# Battery3.net
KiCad netlist of a schematic drawn in Altium Designer
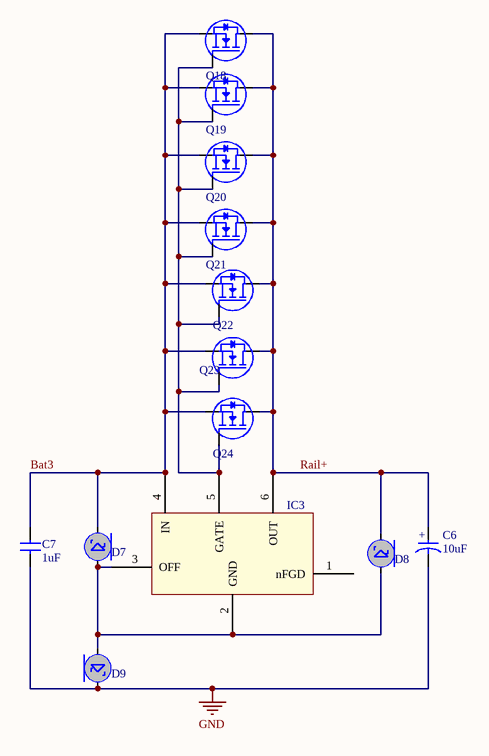
[diagram p0: Battery3.SchDoc]

(export (version "E")
  (design (tool "Eeschema 10.0.6"))
  (components
    (comp (ref "C6")
      (value "10uF")
      (footprint "CAP22uF100V")
      (fields (field (name "Comment") "CapPol"))
      (libsource (lib "SubjuGator8") (part "CapPol"))
    )
    (comp (ref "C7")
      (value "1uF")
      (footprint "CAPC1206")
      (fields (field (name "Comment") "Cap"))
      (libsource (lib "SubjuGator8") (part "Cap"))
    )
    (comp (ref "D7")
      (value "Schottky")
      (footprint "SS110-TP")
      (description "Schottky Diode Template")
      (libsource (lib "SubjuGator8") (part "Schottky"))
    )
    (comp (ref "D8")
      (value "SMBJ100A-13-F")
      (footprint "SMBJ100A-13-F")
      (description "TVS DIODE 100VWM 162VC SMB")
      (libsource (lib "SubjuGator8") (part "SMBJ100A-13-F"))
    )
    (comp (ref "D9")
      (value "Schottky")
      (footprint "SS110-TP")
      (description "Schottky Diode Template")
      (libsource (lib "") (part "Schottky_1"))
    )
    (comp (ref "IC3")
      (value "LM5050MK-2/NOPB")
      (footprint "LM5050MK-2/NOPB")
      (description "IC OR CTRLR N+1 6SOT")
      (libsource (lib "SubjuGator8") (part "LM5050MK-2/NOPB"))
    )
    (comp (ref "Q18")
      (value "CSD19502Q5B")
      (footprint "CSD19502Q5B")
      (description "NEXFET Power MOSFET")
      (libsource (lib "SubjuGator8") (part "CSD19502Q5B"))
    )
    (comp (ref "Q19")
      (value "CSD19502Q5B")
      (footprint "CSD19502Q5B")
      (description "NEXFET Power MOSFET")
      (libsource (lib "SubjuGator8") (part "CSD19502Q5B"))
    )
    (comp (ref "Q20")
      (value "CSD19502Q5B")
      (footprint "CSD19502Q5B")
      (description "NEXFET Power MOSFET")
      (libsource (lib "SubjuGator8") (part "CSD19502Q5B"))
    )
    (comp (ref "Q21")
      (value "CSD19502Q5B")
      (footprint "CSD19502Q5B")
      (description "NEXFET Power MOSFET")
      (libsource (lib "SubjuGator8") (part "CSD19502Q5B"))
    )
    (comp (ref "Q22")
      (value "CSD19502Q5B")
      (footprint "CSD19502Q5B")
      (description "NEXFET Power MOSFET")
      (libsource (lib "SubjuGator8") (part "CSD19502Q5B"))
    )
    (comp (ref "Q23")
      (value "CSD19502Q5B")
      (footprint "CSD19502Q5B")
      (description "NEXFET Power MOSFET")
      (libsource (lib "SubjuGator8") (part "CSD19502Q5B"))
    )
    (comp (ref "Q24")
      (value "CSD19502Q5B")
      (footprint "CSD19502Q5B")
      (description "NEXFET Power MOSFET")
      (libsource (lib "SubjuGator8") (part "CSD19502Q5B"))
    )
  )
  (nets
    (net (code "1") (name "/Bat3") (class "Default")
      (node (ref "C7") (pin "1") (pinfunction "A_1") (pintype "passive"))
      (node (ref "D7") (pin "C") (pinfunction "C_C") (pintype "passive"))
      (node (ref "IC3") (pin "4") (pinfunction "IN_4") (pintype "passive"))
      (node (ref "Q18") (pin "S") (pinfunction "S_S") (pintype "passive"))
      (node (ref "Q19") (pin "S") (pinfunction "S_S") (pintype "passive"))
      (node (ref "Q20") (pin "S") (pinfunction "S_S") (pintype "passive"))
      (node (ref "Q21") (pin "S") (pinfunction "S_S") (pintype "passive"))
      (node (ref "Q22") (pin "S") (pinfunction "S_S") (pintype "passive"))
      (node (ref "Q23") (pin "S") (pinfunction "S_S") (pintype "passive"))
      (node (ref "Q24") (pin "S") (pinfunction "S_S") (pintype "passive"))
    )
    (net (code "2") (name "/Rail+") (class "Default")
      (node (ref "C6") (pin "1") (pinfunction "A_1") (pintype "passive"))
      (node (ref "D8") (pin "C") (pinfunction "C_C") (pintype "passive"))
      (node (ref "IC3") (pin "6") (pinfunction "OUT_6") (pintype "passive"))
      (node (ref "Q18") (pin "D") (pinfunction "D_D") (pintype "passive"))
      (node (ref "Q19") (pin "D") (pinfunction "D_D") (pintype "passive"))
      (node (ref "Q20") (pin "D") (pinfunction "D_D") (pintype "passive"))
      (node (ref "Q21") (pin "D") (pinfunction "D_D") (pintype "passive"))
      (node (ref "Q22") (pin "D") (pinfunction "D_D") (pintype "passive"))
      (node (ref "Q23") (pin "D") (pinfunction "D_D") (pintype "passive"))
      (node (ref "Q24") (pin "D") (pinfunction "D_D") (pintype "passive"))
    )
    (net (code "3") (name "GND") (class "Default")
      (node (ref "C6") (pin "2") (pinfunction "B_2") (pintype "passive"))
      (node (ref "C7") (pin "2") (pinfunction "B_2") (pintype "passive"))
      (node (ref "D9") (pin "C") (pinfunction "C_C") (pintype "passive"))
    )
    (net (code "4") (name "Net-(IC3-GATE)") (class "Default")
      (node (ref "IC3") (pin "5") (pinfunction "GATE_5") (pintype "passive"))
      (node (ref "Q18") (pin "G") (pinfunction "G_G") (pintype "passive"))
      (node (ref "Q19") (pin "G") (pinfunction "G_G") (pintype "passive"))
      (node (ref "Q20") (pin "G") (pinfunction "G_G") (pintype "passive"))
      (node (ref "Q21") (pin "G") (pinfunction "G_G") (pintype "passive"))
      (node (ref "Q22") (pin "G") (pinfunction "G_G") (pintype "passive"))
      (node (ref "Q23") (pin "G") (pinfunction "G_G") (pintype "passive"))
      (node (ref "Q24") (pin "G") (pinfunction "G_G") (pintype "passive"))
    )
    (net (code "5") (name "Net-(IC3-GND)") (class "Default")
      (node (ref "D7") (pin "A") (pinfunction "A_A") (pintype "passive"))
      (node (ref "D8") (pin "A") (pinfunction "A_A") (pintype "passive"))
      (node (ref "D9") (pin "A") (pinfunction "A_A") (pintype "passive"))
      (node (ref "IC3") (pin "2") (pinfunction "GND_2") (pintype "passive"))
      (node (ref "IC3") (pin "3") (pinfunction "OFF_3") (pintype "passive"))
    )
    (net (code "6") (name "unconnected-(IC3-nFGD-Pad1)") (class "Default")
      (node (ref "IC3") (pin "1") (pinfunction "nFGD_1") (pintype "passive"))
    )
  )
)
